# Power.net
KiCad netlist of a schematic drawn in Altium Designer
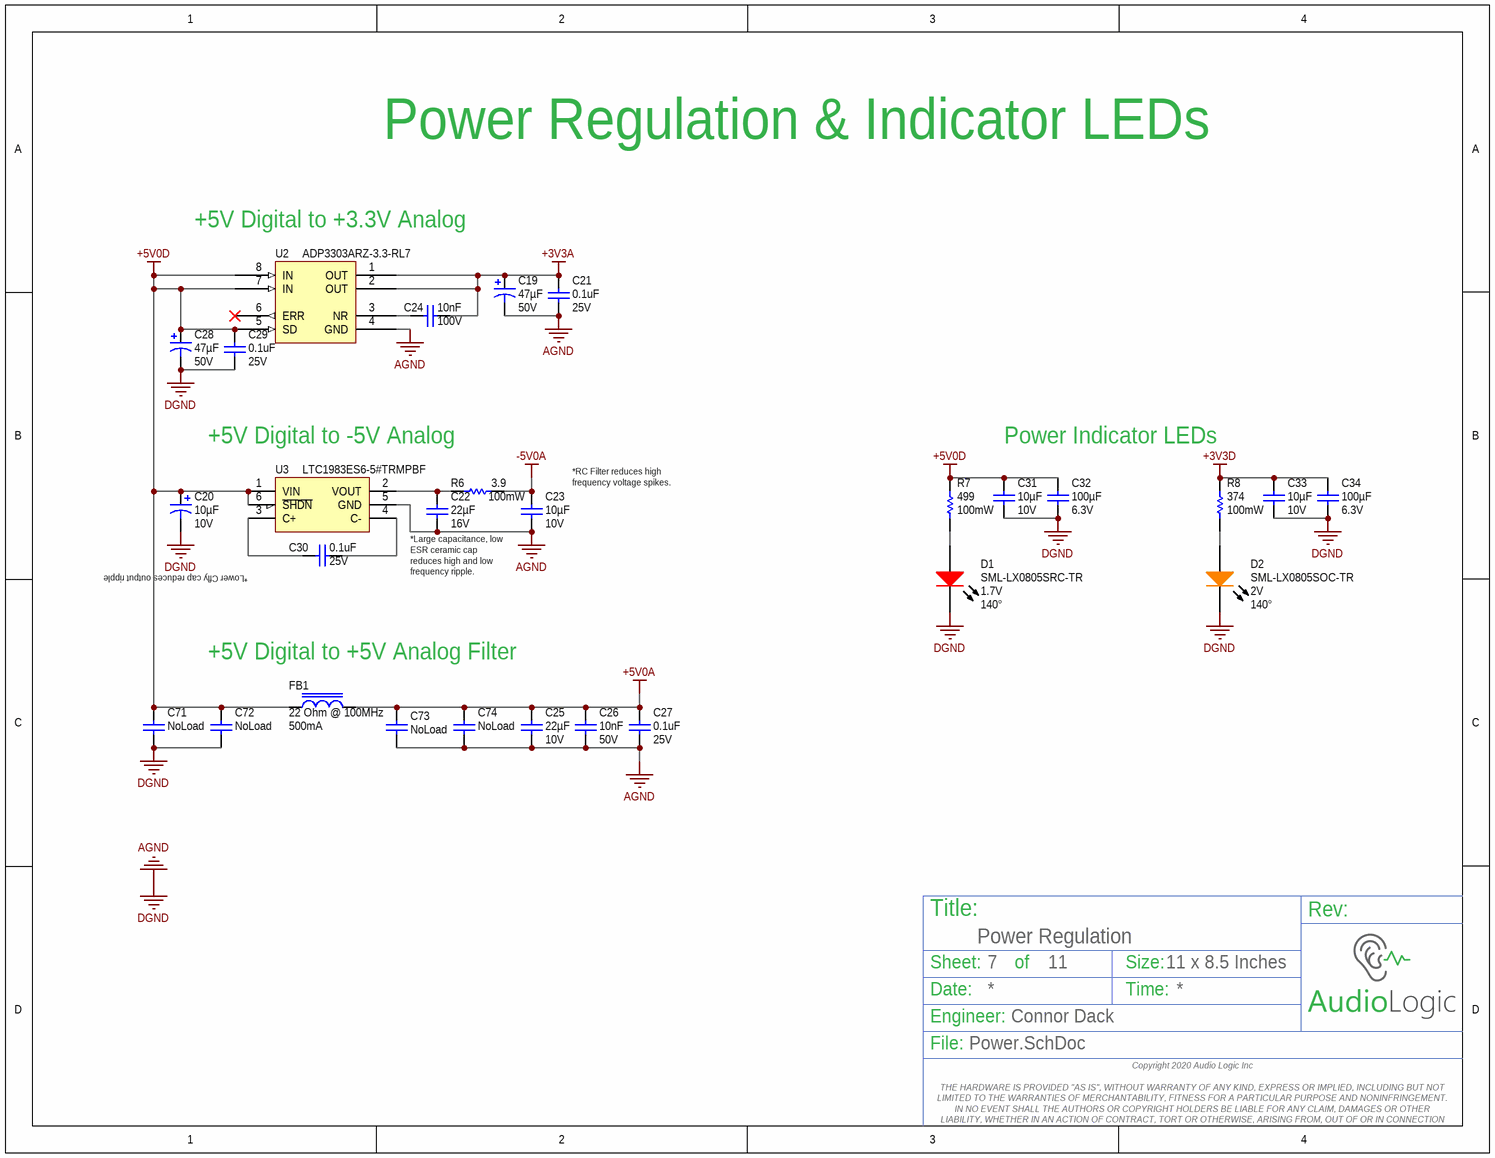
[diagram p0: Power.SchDoc]

(export (version "E")
  (design (tool "Eeschema 10.0.6"))
  (components
    (comp (ref "C19")
      (value "EEE-FT1H470AP")
      (footprint "ALUMCAPC630D_D")
      (description "CAP ALUM 47UF 50V 20% SMD")
      (fields
        (field (name "MANUFACTURER") "Panasonic - ECG")
        (field (name "VOLTAGE RATING") "50V")
        (field (name "TOLERANCE") "±20%")
        (field (name "CAPACITANCE") "47µF")
      )
      (libsource (lib "Schematic_Components") (part "EEE-FT1H470AP"))
    )
    (comp (ref "C20")
      (value "TPSA106K010R0900")
      (footprint "C1206_TANT")
      (description "CAP TANT 10UF 10V 10% 1206")
      (fields
        (field (name "MANUFACTURER") "AVX Corporation")
        (field (name "VOLTAGE - RATED") "10V")
        (field (name "TOLERANCE") "±10%")
        (field (name "CAPACITANCE") "10µF")
      )
      (libsource (lib "Schematic_Components") (part "TPSA106K010R0900"))
    )
    (comp (ref "C21")
      (value "CGA3E2X7R1E104K080AA")
      (footprint "3-0603_L")
      (description "CAP CER 0.1UF 25V X7R 0603")
      (fields
        (field (name "MANUFACTURER") "TDK")
        (field (name "TOLERANCE") "10%")
        (field (name "VOLTAGE RATING") "25V")
        (field (name "CAPACITANCE") "0.1uF")
      )
      (libsource (lib "Schematic_Components_CD") (part "CGA3E2X7R1E104K080AA"))
    )
    (comp (ref "C22")
      (value "C3216X6S1C226M")
      (footprint "C1206")
      (description "CAP CER 22UF 16V 20% X6S 1206")
      (fields
        (field (name "MANUFACTURER") "TDK Corporation")
        (field (name "VOLTAGE - RATED") "16V")
        (field (name "TOLERANCE") "±20%")
        (field (name "CAPACITANCE") "22µF")
      )
      (libsource (lib "Schematic_Components") (part "C3216X6S1C226M"))
    )
    (comp (ref "C23")
      (value "C1608X5R1A106K")
      (footprint "3-0603_L")
      (description "CAP CER 10UF 10V 10% X5R 0603")
      (fields
        (field (name "MANUFACTURER") "TDK Corporation")
        (field (name "VOLTAGE - RATED") "10V")
        (field (name "TOLERANCE") "±10%")
        (field (name "CAPACITANCE") "10µF")
      )
      (libsource (lib "Schematic_Components") (part "C1608X5R1A106K"))
    )
    (comp (ref "C24")
      (value "C1608X7R2A103K080AA")
      (footprint "3-0603_L")
      (description "CAP CER 10000PF 100V X7R 0603")
      (fields
        (field (name "MANUFACTURER") "TDK Corporation")
        (field (name "VOLTAGE - RATED") "100V")
        (field (name "TOLERANCE") "±10%")
        (field (name "CAPACITANCE") "10nF")
      )
      (libsource (lib "Schematic_Components") (part "C1608X7R2A103K080AA"))
    )
    (comp (ref "C25")
      (value "CL21A226KPCLRNC")
      (footprint "6-0805_L")
      (description "CAP CER 22UF 10V X5R 0805")
      (fields
        (field (name "MANUFACTURER") "Samsung Electro-Mechanics America, Inc.")
        (field (name "TOLERANCE") "±10%")
        (field (name "VOLTAGE - RATED") "10V")
        (field (name "CAPACITANCE") "22µF")
      )
      (libsource (lib "Schematic_Components") (part "CL21A226KPCLRNC"))
    )
    (comp (ref "C26")
      (value "C0603C103J5RACTU")
      (footprint "3-0603_L")
      (description "CAP CER 10000PF 50V 5% X7R 0603")
      (fields
        (field (name "MANUFACTURER") "Kemet")
        (field (name "VOLTAGE - RATED") "50V")
        (field (name "TOLERANCE") "±5%")
        (field (name "CAPACITANCE") "10nF")
      )
      (libsource (lib "Schematic_Components") (part "C0603C103J5RACTU"))
    )
    (comp (ref "C27")
      (value "CGA3E2X7R1E104K080AA")
      (footprint "3-0603_L")
      (description "CAP CER 0.1UF 25V X7R 0603")
      (fields
        (field (name "MANUFACTURER") "TDK")
        (field (name "TOLERANCE") "10%")
        (field (name "VOLTAGE RATING") "25V")
        (field (name "CAPACITANCE") "0.1uF")
      )
      (libsource (lib "Schematic_Components_CD") (part "CGA3E2X7R1E104K080AA"))
    )
    (comp (ref "C28")
      (value "EEE-FT1H470AP")
      (footprint "ALUMCAPC630D_D")
      (description "CAP ALUM 47UF 50V 20% SMD")
      (fields
        (field (name "MANUFACTURER") "Panasonic - ECG")
        (field (name "VOLTAGE RATING") "50V")
        (field (name "TOLERANCE") "±20%")
        (field (name "CAPACITANCE") "47µF")
      )
      (libsource (lib "Schematic_Components") (part "EEE-FT1H470AP"))
    )
    (comp (ref "C29")
      (value "CGA3E2X7R1E104K080AA")
      (footprint "3-0603_L")
      (description "CAP CER 0.1UF 25V X7R 0603")
      (fields
        (field (name "MANUFACTURER") "TDK")
        (field (name "TOLERANCE") "10%")
        (field (name "VOLTAGE RATING") "25V")
        (field (name "CAPACITANCE") "0.1uF")
      )
      (libsource (lib "Schematic_Components_CD") (part "CGA3E2X7R1E104K080AA"))
    )
    (comp (ref "C30")
      (value "CGA3E2X7R1E104K080AA")
      (footprint "3-0603_L")
      (description "CAP CER 0.1UF 25V X7R 0603")
      (fields
        (field (name "MANUFACTURER") "TDK")
        (field (name "TOLERANCE") "10%")
        (field (name "VOLTAGE RATING") "25V")
        (field (name "CAPACITANCE") "0.1uF")
      )
      (libsource (lib "Schematic_Components_CD") (part "CGA3E2X7R1E104K080AA"))
    )
    (comp (ref "C31")
      (value "C1608X5R1A106K")
      (footprint "3-0603_L")
      (description "CAP CER 10UF 10V 10% X5R 0603")
      (fields
        (field (name "MANUFACTURER") "TDK Corporation")
        (field (name "VOLTAGE - RATED") "10V")
        (field (name "TOLERANCE") "±10%")
        (field (name "CAPACITANCE") "10µF")
      )
      (libsource (lib "Schematic_Components") (part "C1608X5R1A106K"))
    )
    (comp (ref "C32")
      (value "CL32X107MQVNNNE")
      (footprint "C1210X25_L")
      (description "100µF 6.3V Ceramic Capacitor X6S 1210 (3225 Metric) 0.126\" L x 0.098\" W (3.20mm x 2.50mm)")
      (fields
        (field (name "MANUFACTURER") "Samsung Electro-Mechanics America, Inc.")
        (field (name "TOLERANCE") "±20%")
        (field (name "VOLTAGE - RATED") "6.3V")
        (field (name "CAPACITANCE") "100µF")
      )
      (libsource (lib "Schematic_Components") (part "CL32X107MQVNNNE"))
    )
    (comp (ref "C33")
      (value "C1608X5R1A106K")
      (footprint "3-0603_L")
      (description "CAP CER 10UF 10V 10% X5R 0603")
      (fields
        (field (name "MANUFACTURER") "TDK Corporation")
        (field (name "VOLTAGE - RATED") "10V")
        (field (name "TOLERANCE") "±10%")
        (field (name "CAPACITANCE") "10µF")
      )
      (libsource (lib "Schematic_Components") (part "C1608X5R1A106K"))
    )
    (comp (ref "C34")
      (value "CL32X107MQVNNNE")
      (footprint "C1210X25_L")
      (description "100µF 6.3V Ceramic Capacitor X6S 1210 (3225 Metric) 0.126\" L x 0.098\" W (3.20mm x 2.50mm)")
      (fields
        (field (name "MANUFACTURER") "Samsung Electro-Mechanics America, Inc.")
        (field (name "TOLERANCE") "±20%")
        (field (name "VOLTAGE - RATED") "6.3V")
        (field (name "CAPACITANCE") "100µF")
      )
      (libsource (lib "Schematic_Components") (part "CL32X107MQVNNNE"))
    )
    (comp (ref "C71")
      (value "CAP 0603")
      (footprint "3-0603_L_DNP")
      (description "CAP 0603 SMD - NoLoad")
      (fields (field (name "CAPACITANCE") "NoLoad"))
      (libsource (lib "Schematic_Components_CD") (part "CAP 0603"))
    )
    (comp (ref "C72")
      (value "CAP 0603")
      (footprint "3-0603_L_DNP")
      (description "CAP 0603 SMD - NoLoad")
      (fields (field (name "CAPACITANCE") "NoLoad"))
      (libsource (lib "Schematic_Components_CD") (part "CAP 0603"))
    )
    (comp (ref "C73")
      (value "CAP 0603")
      (footprint "3-0603_L_DNP")
      (description "CAP 0603 SMD - NoLoad")
      (fields (field (name "CAPACITANCE") "NoLoad"))
      (libsource (lib "Schematic_Components_CD") (part "CAP 0603"))
    )
    (comp (ref "C74")
      (value "CAP 0603")
      (footprint "3-0603_L_DNP")
      (description "CAP 0603 SMD - NoLoad")
      (fields (field (name "CAPACITANCE") "NoLoad"))
      (libsource (lib "Schematic_Components_CD") (part "CAP 0603"))
    )
    (comp (ref "D1")
      (value "SML-LX0805SRC-TR")
      (footprint "DIOM2012X12L_RED")
      (description "LED 660NM SUPER RED CLR 0805 T/R")
      (fields
        (field (name "MANUFACTURER") "Lumex Opto/Components Inc")
        (field (name "MANUFACTURER PART NUMBER") "SML-LX0805SRC-TR")
        (field (name "VOLTAGE - FORWARD (VF) (TYP)") "1.7V")
        (field (name "VIEWING ANGLE") "140°")
      )
      (libsource (lib "Schematic_Components") (part "LED_RED 4"))
    )
    (comp (ref "D2")
      (value "SML-LX0805SOC-TR")
      (footprint "DIOM2012X12L_ORANGE")
      (description "LED 610NM SUPER ORANGE 0805 SMD")
      (fields
        (field (name "MANUFACTURER") "Lumex Opto/Components Inc")
        (field (name "MANUFACTURER PART NUMBER") "SML-LX0805SOC-TR")
        (field (name "VOLTAGE - FORWARD (VF) (TYP)") "2V")
        (field (name "VIEWING ANGLE") "140°")
      )
      (libsource (lib "Schematic_Components") (part "LED_ORANGE 3"))
    )
    (comp (ref "FB1")
      (value "BLM18BA220SN1D")
      (footprint "3-0603_L")
      (description "FERRITE CHIP 22 OHM 500MA 0603")
      (fields
        (field (name "MANUFACTURER") "Murata Electronics North America")
        (field (name "CURRENT RATING") "500mA")
        (field (name "IMPEDANCE @ FREQUENCY") "22 Ohm @ 100MHz")
      )
      (libsource (lib "Schematic_Components") (part "BLM18BA220SN1D"))
    )
    (comp (ref "R6")
      (value "ERJ-3RQF3R9V")
      (footprint "3-0603_R_L")
      (description "RES 3.9 OHM 1/10W 1% 0603 SMD")
      (fields
        (field (name "MANUFACTURER") "Panasonic Electronic Components")
        (field (name "TOLERANCE") "±1%")
        (field (name "POWER (WATTS)") "100mW")
        (field (name "RESISTANCE (OHMS)") "3.9")
      )
      (libsource (lib "Schematic_Components") (part "ERJ-3RQF3R9V"))
    )
    (comp (ref "R7")
      (value "ERJ-3EKF4990V")
      (footprint "3-0603_R_L")
      (description "RES 499 OHM 1/10W 1% 0603 SMD")
      (fields
        (field (name "MANUFACTURER") "Panasonic - ECG")
        (field (name "POWER (WATTS)") "100mW")
        (field (name "TOLERANCE") "±1%")
        (field (name "RESISTANCE (OHMS)") "499")
      )
      (libsource (lib "Schematic_Components") (part "ERJ-3EKF4990V"))
    )
    (comp (ref "R8")
      (value "ERJ-3EKF3740V")
      (footprint "3-0603_R_L")
      (description "RES SMD 374 OHM 1% 1/10W 0603")
      (fields
        (field (name "MANUFACTURER") "Panasonic Electronic Components")
        (field (name "TOLERANCE") "±1%")
        (field (name "POWER (WATTS)") "100mW")
        (field (name "RESISTANCE (OHMS)") "374")
      )
      (libsource (lib "Schematic_Components") (part "ERJ-3EKF3740V"))
    )
    (comp (ref "U2")
      (value "ADP3303ARZ-3.3-RL7")
      (footprint "SOIC127P600X175-8N")
      (description "Linear Voltage Regulator IC Positive Fixed 1 Output 3.3V 200mA 8-SOIC")
      (fields
        (field (name "MANUFACTURER") "Analog Devices Inc.")
        (field (name "MANUFACTURER PART NUMBER") "ADP3303ARZ-3.3-RL7")
      )
      (libsource (lib "Schematic_Components_CD") (part "ADP3303ARZ-3.3-RL7"))
    )
    (comp (ref "U3")
      (value "LTC1983ES6-5#TRMPBF")
      (footprint "SOT23-6_L")
      (description "IC REG SWITCHD CAP INV -5V SOT23")
      (fields
        (field (name "MANUFACTURER") "Linear Technology")
        (field (name "MANUFACTURER PART NUMBER") "LTC1983ES6-5#TRMPBF")
      )
      (libsource (lib "Schematic_Components") (part "LTC1983ES6-5#TRMPBF"))
    )
  )
  (nets
    (net (code "1") (name "+3V3A") (class "Default")
      (node (ref "C19") (pin "1") (pinfunction "P_1") (pintype "passive"))
      (node (ref "C21") (pin "1") (pinfunction "1_1") (pintype "passive"))
      (node (ref "C24") (pin "1") (pinfunction "1_1") (pintype "passive"))
      (node (ref "U2") (pin "1") (pinfunction "OUT_1") (pintype "passive"))
      (node (ref "U2") (pin "2") (pinfunction "OUT_2") (pintype "passive"))
    )
    (net (code "2") (name "+3V3D") (class "Default")
      (node (ref "C33") (pin "2") (pinfunction "2_2") (pintype "passive"))
      (node (ref "C34") (pin "2") (pinfunction "2_2") (pintype "passive"))
      (node (ref "R8") (pin "2") (pinfunction "2_2") (pintype "passive"))
    )
    (net (code "3") (name "+5V0A") (class "Default")
      (node (ref "C25") (pin "2") (pinfunction "2_2") (pintype "passive"))
      (node (ref "C26") (pin "2") (pinfunction "2_2") (pintype "passive"))
      (node (ref "C27") (pin "1") (pinfunction "1_1") (pintype "passive"))
      (node (ref "C73") (pin "2") (pinfunction "2_2") (pintype "passive"))
      (node (ref "C74") (pin "2") (pinfunction "2_2") (pintype "passive"))
      (node (ref "FB1") (pin "2") (pinfunction "2_2") (pintype "passive"))
    )
    (net (code "4") (name "+5V0D") (class "Default")
      (node (ref "C20") (pin "1") (pinfunction "P_1") (pintype "passive"))
      (node (ref "C28") (pin "1") (pinfunction "P_1") (pintype "passive"))
      (node (ref "C29") (pin "1") (pinfunction "1_1") (pintype "passive"))
      (node (ref "C31") (pin "2") (pinfunction "2_2") (pintype "passive"))
      (node (ref "C32") (pin "2") (pinfunction "2_2") (pintype "passive"))
      (node (ref "C71") (pin "2") (pinfunction "2_2") (pintype "passive"))
      (node (ref "C72") (pin "2") (pinfunction "2_2") (pintype "passive"))
      (node (ref "FB1") (pin "1") (pinfunction "1_1") (pintype "passive"))
      (node (ref "R7") (pin "2") (pinfunction "2_2") (pintype "passive"))
      (node (ref "U2") (pin "5") (pinfunction "SD_5") (pintype "input"))
      (node (ref "U2") (pin "7") (pinfunction "IN_7") (pintype "input"))
      (node (ref "U2") (pin "8") (pinfunction "IN_8") (pintype "input"))
      (node (ref "U3") (pin "1") (pinfunction "VIN_1") (pintype "power_in"))
      (node (ref "U3") (pin "6") (pinfunction "SHDN_6") (pintype "passive"))
    )
    (net (code "5") (name "-5V0A") (class "Default")
      (node (ref "C23") (pin "2") (pinfunction "2_2") (pintype "passive"))
      (node (ref "R6") (pin "2") (pinfunction "2_2") (pintype "passive"))
    )
    (net (code "6") (name "AGND") (class "Default")
      (node (ref "C19") (pin "2") (pinfunction "N_2") (pintype "passive"))
      (node (ref "C20") (pin "2") (pinfunction "N_2") (pintype "passive"))
      (node (ref "C21") (pin "2") (pinfunction "2_2") (pintype "passive"))
      (node (ref "C22") (pin "1") (pinfunction "1_1") (pintype "passive"))
      (node (ref "C23") (pin "1") (pinfunction "1_1") (pintype "passive"))
      (node (ref "C25") (pin "1") (pinfunction "1_1") (pintype "passive"))
      (node (ref "C26") (pin "1") (pinfunction "1_1") (pintype "passive"))
      (node (ref "C27") (pin "2") (pinfunction "2_2") (pintype "passive"))
      (node (ref "C28") (pin "2") (pinfunction "N_2") (pintype "passive"))
      (node (ref "C29") (pin "2") (pinfunction "2_2") (pintype "passive"))
      (node (ref "C31") (pin "1") (pinfunction "1_1") (pintype "passive"))
      (node (ref "C32") (pin "1") (pinfunction "1_1") (pintype "passive"))
      (node (ref "C33") (pin "1") (pinfunction "1_1") (pintype "passive"))
      (node (ref "C34") (pin "1") (pinfunction "1_1") (pintype "passive"))
      (node (ref "C71") (pin "1") (pinfunction "1_1") (pintype "passive"))
      (node (ref "C72") (pin "1") (pinfunction "1_1") (pintype "passive"))
      (node (ref "C73") (pin "1") (pinfunction "1_1") (pintype "passive"))
      (node (ref "C74") (pin "1") (pinfunction "1_1") (pintype "passive"))
      (node (ref "D1") (pin "2") (pinfunction "K_2") (pintype "passive"))
      (node (ref "D2") (pin "2") (pinfunction "K_2") (pintype "passive"))
      (node (ref "U2") (pin "4") (pinfunction "GND_4") (pintype "passive"))
      (node (ref "U3") (pin "5") (pinfunction "GND_5") (pintype "passive"))
    )
    (net (code "7") (name "Net-(D1-A)") (class "Default")
      (node (ref "D1") (pin "1") (pinfunction "A_1") (pintype "passive"))
      (node (ref "R7") (pin "1") (pinfunction "1_1") (pintype "passive"))
    )
    (net (code "8") (name "Net-(D2-A)") (class "Default")
      (node (ref "D2") (pin "1") (pinfunction "A_1") (pintype "passive"))
      (node (ref "R8") (pin "1") (pinfunction "1_1") (pintype "passive"))
    )
    (net (code "9") (name "Net-(U2-NR)") (class "Default")
      (node (ref "C24") (pin "2") (pinfunction "2_2") (pintype "passive"))
      (node (ref "U2") (pin "3") (pinfunction "NR_3") (pintype "passive"))
    )
    (net (code "10") (name "Net-(U3-C+)") (class "Default")
      (node (ref "C30") (pin "2") (pinfunction "2_2") (pintype "passive"))
      (node (ref "U3") (pin "3") (pinfunction "C+_3") (pintype "passive"))
    )
    (net (code "11") (name "Net-(U3-C-)") (class "Default")
      (node (ref "C30") (pin "1") (pinfunction "1_1") (pintype "passive"))
      (node (ref "U3") (pin "4") (pinfunction "C-_4") (pintype "passive"))
    )
    (net (code "12") (name "Net-(U3-VOUT)") (class "Default")
      (node (ref "C22") (pin "2") (pinfunction "2_2") (pintype "passive"))
      (node (ref "R6") (pin "1") (pinfunction "1_1") (pintype "passive"))
      (node (ref "U3") (pin "2") (pinfunction "VOUT_2") (pintype "power_in"))
    )
    (net (code "13") (name "unconnected-(U2-ERR-Pad6)") (class "Default")
      (node (ref "U2") (pin "6") (pinfunction "ERR_6") (pintype "output+no_connect"))
    )
  )
)
